# lawn_manager_v1_0.net
KiCad netlist of a schematic drawn in EAGLE
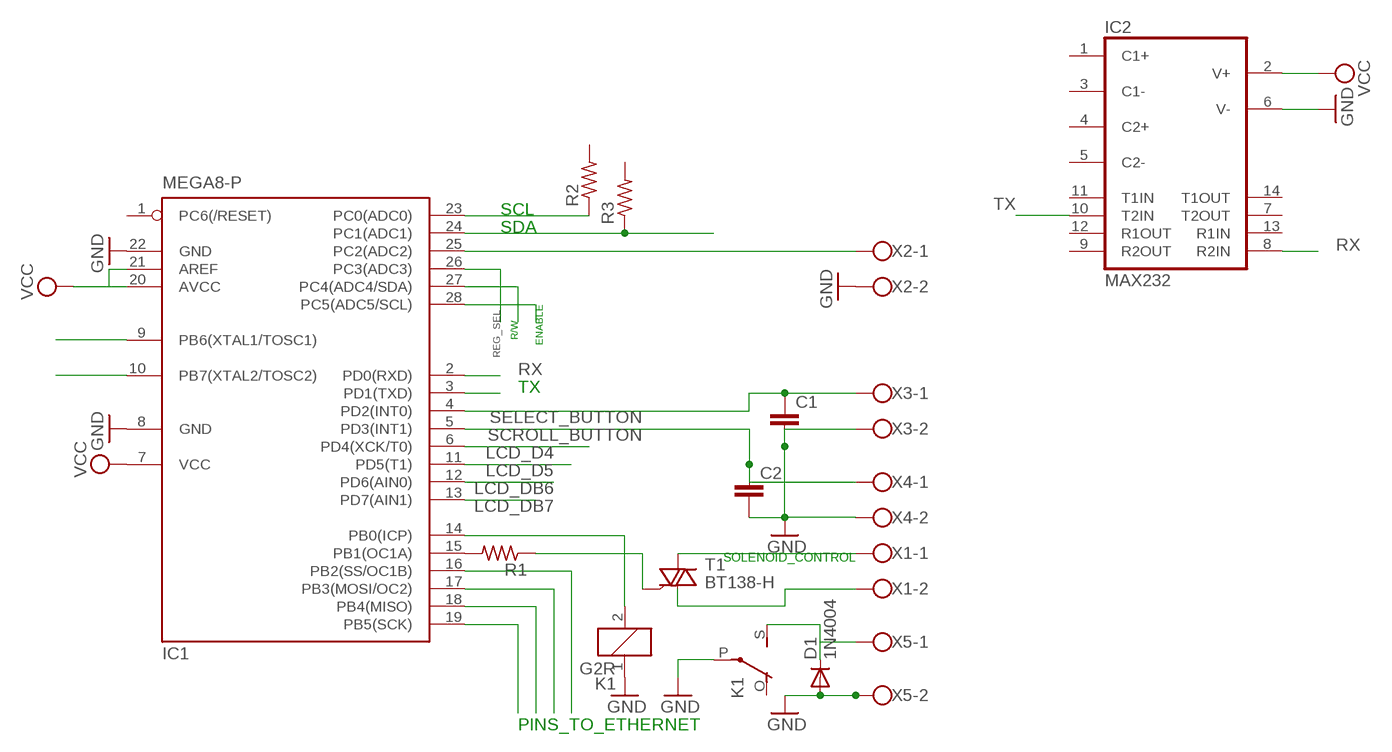
[diagram p0: schematic, sheet 1]

(export (version "E")
  (design (tool "Eeschema 10.0.6"))
  (components
    (comp (ref "C1")
      (value "C2.5/2")
      (footprint "eagle-import:C2.5-2")
      (libsource (lib "eagle-import") (part "C2.5/2"))
    )
    (comp (ref "C2")
      (value "C2.5/2")
      (footprint "eagle-import:C2.5-2")
      (libsource (lib "eagle-import") (part "C2.5/2"))
    )
    (comp (ref "D1")
      (value "1N4004")
      (footprint "eagle-import:DO41-10")
      (libsource (lib "eagle-import") (part "1N4004"))
    )
    (comp (ref "IC1")
      (value "MEGA8-P")
      (footprint "eagle-import:DIL28-3")
      (libsource (lib "eagle-import") (part "MEGA8-P"))
    )
    (comp (ref "IC2")
      (value "MAX232")
      (footprint "eagle-import:DIL16")
      (fields (field (name "MF") "MAXIM") (field (name "MPN") "MAX232ACPE+"))
      (libsource (lib "eagle-import") (part "MAX232"))
    )
    (comp (ref "K1")
      (value "G2R")
      (footprint "eagle-import:G2R")
      (libsource (lib "eagle-import") (part "G2R"))
    )
    (comp (ref "R1")
      (value "R-US_0207/10")
      (footprint "eagle-import:0207_10")
      (libsource (lib "eagle-import") (part "R-US_0207/10"))
    )
    (comp (ref "R2")
      (value "R-US_0204/5")
      (footprint "eagle-import:0204_5")
      (libsource (lib "eagle-import") (part "R-US_0204/5"))
    )
    (comp (ref "R3")
      (value "R-US_0204/5")
      (footprint "eagle-import:0204_5")
      (libsource (lib "eagle-import") (part "R-US_0204/5"))
    )
    (comp (ref "T1")
      (value "BT138-H")
      (footprint "eagle-import:TO220BH")
      (libsource (lib "eagle-import") (part "BT138-H"))
    )
    (comp (ref "X1")
      (value "W237-102")
      (footprint "eagle-import:W237-102")
      (fields (field (name "MPN") "237-102"))
      (libsource (lib "eagle-import") (part "W237-102"))
    )
    (comp (ref "X2")
      (value "W237-102")
      (footprint "eagle-import:W237-102")
      (fields (field (name "MPN") "237-102"))
      (libsource (lib "eagle-import") (part "W237-102"))
    )
    (comp (ref "X3")
      (value "W237-102")
      (footprint "eagle-import:W237-102")
      (fields (field (name "MPN") "237-102"))
      (libsource (lib "eagle-import") (part "W237-102"))
    )
    (comp (ref "X4")
      (value "W237-102")
      (footprint "eagle-import:W237-102")
      (fields (field (name "MPN") "237-102"))
      (libsource (lib "eagle-import") (part "W237-102"))
    )
    (comp (ref "X5")
      (value "W237-102")
      (footprint "eagle-import:W237-102")
      (fields (field (name "MPN") "237-102"))
      (libsource (lib "eagle-import") (part "W237-102"))
    )
  )
  (nets
    (net (code "1") (name "/ENABLE") (class "Default")
      (node (ref "IC1") (pin "28") (pinfunction "PC5(ADC5/SCL)_28") (pintype "bidirectional"))
    )
    (net (code "2") (name "/LCD_D4") (class "Default")
      (node (ref "IC1") (pin "6") (pinfunction "PD4(XCK/T0)_6") (pintype "bidirectional"))
    )
    (net (code "3") (name "/LCD_D5") (class "Default")
      (node (ref "IC1") (pin "11") (pinfunction "PD5(T1)_11") (pintype "bidirectional"))
    )
    (net (code "4") (name "/LCD_DB6") (class "Default")
      (node (ref "IC1") (pin "12") (pinfunction "PD6(AIN0)_12") (pintype "bidirectional"))
    )
    (net (code "5") (name "/LCD_DB7") (class "Default")
      (node (ref "IC1") (pin "13") (pinfunction "PD7(AIN1)_13") (pintype "bidirectional"))
    )
    (net (code "6") (name "/PINS_TO_ETHERNET") (class "Default")
      (node (ref "IC1") (pin "19") (pinfunction "PB5(SCK)_19") (pintype "bidirectional"))
    )
    (net (code "7") (name "/REG_SEL") (class "Default")
      (node (ref "IC1") (pin "26") (pinfunction "PC3(ADC3)_26") (pintype "bidirectional"))
    )
    (net (code "8") (name "/RX") (class "Default")
      (node (ref "IC1") (pin "2") (pinfunction "PD0(RXD)_2") (pintype "bidirectional"))
      (node (ref "IC2") (pin "8") (pinfunction "R2IN_8") (pintype "input"))
    )
    (net (code "9") (name "/R{slash}W") (class "Default")
      (node (ref "IC1") (pin "27") (pinfunction "PC4(ADC4/SDA)_27") (pintype "bidirectional"))
    )
    (net (code "10") (name "/SCL") (class "Default")
      (node (ref "IC1") (pin "23") (pinfunction "PC0(ADC0)_23") (pintype "bidirectional"))
      (node (ref "R2") (pin "1") (pinfunction "1_1") (pintype "passive"))
    )
    (net (code "11") (name "/SCROLL_BUTTON") (class "Default")
      (node (ref "C2") (pin "1") (pinfunction "1_1") (pintype "passive"))
      (node (ref "IC1") (pin "5") (pinfunction "PD3(INT1)_5") (pintype "bidirectional"))
      (node (ref "X4") (pin "1") (pinfunction "KL_1") (pintype "passive"))
    )
    (net (code "12") (name "/SDA") (class "Default")
      (node (ref "IC1") (pin "24") (pinfunction "PC1(ADC1)_24") (pintype "bidirectional"))
      (node (ref "R3") (pin "1") (pinfunction "1_1") (pintype "passive"))
    )
    (net (code "13") (name "/SELECT_BUTTON") (class "Default")
      (node (ref "C1") (pin "1") (pinfunction "1_1") (pintype "passive"))
      (node (ref "IC1") (pin "4") (pinfunction "PD2(INT0)_4") (pintype "bidirectional"))
      (node (ref "X3") (pin "1") (pinfunction "KL_1") (pintype "passive"))
    )
    (net (code "14") (name "/SOLENOID_CONTROL") (class "Default")
      (node (ref "T1") (pin "T2") (pinfunction "A2_T2") (pintype "passive"))
      (node (ref "X1") (pin "1") (pinfunction "KL_1") (pintype "passive"))
    )
    (net (code "15") (name "/TX") (class "Default")
      (node (ref "IC1") (pin "3") (pinfunction "PD1(TXD)_3") (pintype "bidirectional"))
      (node (ref "IC2") (pin "10") (pinfunction "T2IN_10") (pintype "input"))
    )
    (net (code "16") (name "GND") (class "Default")
      (node (ref "C1") (pin "2") (pinfunction "2_2") (pintype "passive"))
      (node (ref "C2") (pin "2") (pinfunction "2_2") (pintype "passive"))
      (node (ref "D1") (pin "A") (pinfunction "A_A") (pintype "passive"))
      (node (ref "IC1") (pin "22") (pinfunction "GND_22") (pintype "power_in"))
      (node (ref "IC1") (pin "8") (pinfunction "GND_8") (pintype "power_in"))
      (node (ref "IC2") (pin "6") (pinfunction "V-_6") (pintype "bidirectional"))
      (node (ref "K1") (pin "1") (pinfunction "1_1") (pintype "passive"))
      (node (ref "K1") (pin "P") (pinfunction "P_P") (pintype "passive"))
      (node (ref "X2") (pin "2") (pinfunction "KL_2") (pintype "passive"))
      (node (ref "X3") (pin "2") (pinfunction "KL_2") (pintype "passive"))
      (node (ref "X4") (pin "2") (pinfunction "KL_2") (pintype "passive"))
      (node (ref "X5") (pin "2") (pinfunction "KL_2") (pintype "passive"))
    )
    (net (code "17") (name "Net-(IC1-PB0(ICP))") (class "Default")
      (node (ref "IC1") (pin "14") (pinfunction "PB0(ICP)_14") (pintype "bidirectional"))
      (node (ref "K1") (pin "2") (pinfunction "2_2") (pintype "passive"))
    )
    (net (code "18") (name "Net-(IC1-PB1(OC1A))") (class "Default")
      (node (ref "IC1") (pin "15") (pinfunction "PB1(OC1A)_15") (pintype "bidirectional"))
      (node (ref "R1") (pin "2") (pinfunction "2_2") (pintype "passive"))
    )
    (net (code "19") (name "Net-(IC1-PC2(ADC2))") (class "Default")
      (node (ref "IC1") (pin "25") (pinfunction "PC2(ADC2)_25") (pintype "bidirectional"))
      (node (ref "X2") (pin "1") (pinfunction "KL_1") (pintype "passive"))
    )
    (net (code "20") (name "Net-(R1-Pad1)") (class "Default")
      (node (ref "R1") (pin "1") (pinfunction "1_1") (pintype "passive"))
      (node (ref "T1") (pin "G") (pinfunction "G_G") (pintype "passive"))
    )
    (net (code "21") (name "Net-(T1-A1)") (class "Default")
      (node (ref "T1") (pin "T1") (pinfunction "A1_T1") (pintype "passive"))
      (node (ref "X1") (pin "2") (pinfunction "KL_2") (pintype "passive"))
    )
    (net (code "22") (name "Net-(X5A-KL)") (class "Default")
      (node (ref "D1") (pin "C") (pinfunction "C_C") (pintype "passive"))
      (node (ref "K1") (pin "S") (pinfunction "S_S") (pintype "passive"))
      (node (ref "X5") (pin "1") (pinfunction "KL_1") (pintype "passive"))
    )
    (net (code "23") (name "VCC") (class "Default")
      (node (ref "IC1") (pin "20") (pinfunction "AVCC_20") (pintype "power_in"))
      (node (ref "IC1") (pin "21") (pinfunction "AREF_21") (pintype "passive"))
      (node (ref "IC1") (pin "7") (pinfunction "VCC_7") (pintype "power_in"))
      (node (ref "IC2") (pin "2") (pinfunction "V+_2") (pintype "bidirectional"))
    )
    (net (code "24") (name "unconnected-(IC1-PB2(SS{slash}OC1B)-Pad16)") (class "Default")
      (node (ref "IC1") (pin "16") (pinfunction "PB2(SS/OC1B)_16") (pintype "bidirectional"))
    )
    (net (code "25") (name "unconnected-(IC1-PB3(MOSI{slash}OC2)-Pad17)") (class "Default")
      (node (ref "IC1") (pin "17") (pinfunction "PB3(MOSI/OC2)_17") (pintype "bidirectional"))
    )
    (net (code "26") (name "unconnected-(IC1-PB4(MISO)-Pad18)") (class "Default")
      (node (ref "IC1") (pin "18") (pinfunction "PB4(MISO)_18") (pintype "bidirectional"))
    )
    (net (code "27") (name "unconnected-(IC1-PB6(XTAL1{slash}TOSC1)-Pad9)") (class "Default")
      (node (ref "IC1") (pin "9") (pinfunction "PB6(XTAL1/TOSC1)_9") (pintype "bidirectional"))
    )
    (net (code "28") (name "unconnected-(IC1-PB7(XTAL2{slash}TOSC2)-Pad10)") (class "Default")
      (node (ref "IC1") (pin "10") (pinfunction "PB7(XTAL2/TOSC2)_10") (pintype "bidirectional"))
    )
    (net (code "29") (name "unconnected-(IC1-PC6({slash}RESET)-Pad1)") (class "Default")
      (node (ref "IC1") (pin "1") (pinfunction "PC6(/RESET)_1") (pintype "bidirectional"))
    )
    (net (code "30") (name "unconnected-(IC2A-C1+-Pad1)") (class "Default")
      (node (ref "IC2") (pin "1") (pinfunction "C1+_1") (pintype "bidirectional"))
    )
    (net (code "31") (name "unconnected-(IC2A-C1--Pad3)") (class "Default")
      (node (ref "IC2") (pin "3") (pinfunction "C1-_3") (pintype "bidirectional"))
    )
    (net (code "32") (name "unconnected-(IC2A-C2+-Pad4)") (class "Default")
      (node (ref "IC2") (pin "4") (pinfunction "C2+_4") (pintype "bidirectional"))
    )
    (net (code "33") (name "unconnected-(IC2A-C2--Pad5)") (class "Default")
      (node (ref "IC2") (pin "5") (pinfunction "C2-_5") (pintype "bidirectional"))
    )
    (net (code "34") (name "unconnected-(IC2A-R1IN-Pad13)") (class "Default")
      (node (ref "IC2") (pin "13") (pinfunction "R1IN_13") (pintype "input"))
    )
    (net (code "35") (name "unconnected-(IC2A-R1OUT-Pad12)") (class "Default")
      (node (ref "IC2") (pin "12") (pinfunction "R1OUT_12") (pintype "output"))
    )
    (net (code "36") (name "unconnected-(IC2A-R2OUT-Pad9)") (class "Default")
      (node (ref "IC2") (pin "9") (pinfunction "R2OUT_9") (pintype "output"))
    )
    (net (code "37") (name "unconnected-(IC2A-T1IN-Pad11)") (class "Default")
      (node (ref "IC2") (pin "11") (pinfunction "T1IN_11") (pintype "input"))
    )
    (net (code "38") (name "unconnected-(IC2A-T1OUT-Pad14)") (class "Default")
      (node (ref "IC2") (pin "14") (pinfunction "T1OUT_14") (pintype "output"))
    )
    (net (code "39") (name "unconnected-(IC2A-T2OUT-Pad7)") (class "Default")
      (node (ref "IC2") (pin "7") (pinfunction "T2OUT_7") (pintype "output"))
    )
    (net (code "40") (name "unconnected-(K1-PadO)") (class "Default")
      (node (ref "K1") (pin "O") (pinfunction "O_O") (pintype "passive"))
    )
    (net (code "41") (name "unconnected-(R2-Pad2)") (class "Default")
      (node (ref "R2") (pin "2") (pinfunction "2_2") (pintype "passive"))
    )
    (net (code "42") (name "unconnected-(R3-Pad2)") (class "Default")
      (node (ref "R3") (pin "2") (pinfunction "2_2") (pintype "passive"))
    )
  )
)
